# quad_sensor_adapter.net
KiCad netlist of a schematic drawn in EAGLE
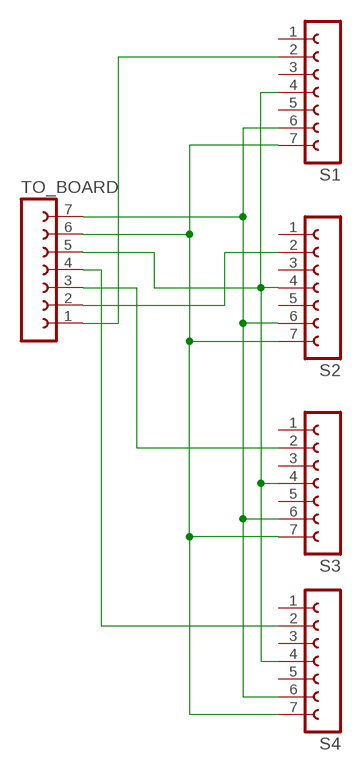
[diagram p0: schematic, sheet 1]

(export (version "E")
  (design (tool "Eeschema 10.0.6"))
  (components
    (comp (ref "S1")
      (value "FE07-1")
      (footprint "eagle-import:FE07")
      (libsource (lib "eagle-import") (part "FE07-1"))
    )
    (comp (ref "S2")
      (value "FE07-1")
      (footprint "eagle-import:FE07")
      (libsource (lib "eagle-import") (part "FE07-1"))
    )
    (comp (ref "S3")
      (value "FE07-1")
      (footprint "eagle-import:FE07")
      (libsource (lib "eagle-import") (part "FE07-1"))
    )
    (comp (ref "S4")
      (value "FE07-1")
      (footprint "eagle-import:FE07")
      (libsource (lib "eagle-import") (part "FE07-1"))
    )
    (comp (ref "TO_BOARD")
      (value "FE07-1")
      (footprint "eagle-import:FE07")
      (libsource (lib "eagle-import") (part "FE07-1"))
    )
  )
  (nets
    (net (code "1") (name "Net-(S1-Pad2)") (class "Default")
      (node (ref "S1") (pin "2") (pinfunction "2_2") (pintype "passive"))
      (node (ref "TO_BOARD") (pin "1") (pinfunction "1_1") (pintype "passive"))
    )
    (net (code "2") (name "Net-(S1-Pad4)") (class "Default")
      (node (ref "S1") (pin "4") (pinfunction "4_4") (pintype "passive"))
      (node (ref "S2") (pin "4") (pinfunction "4_4") (pintype "passive"))
      (node (ref "S3") (pin "4") (pinfunction "4_4") (pintype "passive"))
      (node (ref "S4") (pin "4") (pinfunction "4_4") (pintype "passive"))
      (node (ref "TO_BOARD") (pin "5") (pinfunction "5_5") (pintype "passive"))
    )
    (net (code "3") (name "Net-(S1-Pad6)") (class "Default")
      (node (ref "S1") (pin "6") (pinfunction "6_6") (pintype "passive"))
      (node (ref "S2") (pin "6") (pinfunction "6_6") (pintype "passive"))
      (node (ref "S3") (pin "6") (pinfunction "6_6") (pintype "passive"))
      (node (ref "S4") (pin "6") (pinfunction "6_6") (pintype "passive"))
      (node (ref "TO_BOARD") (pin "7") (pinfunction "7_7") (pintype "passive"))
    )
    (net (code "4") (name "Net-(S1-Pad7)") (class "Default")
      (node (ref "S1") (pin "7") (pinfunction "7_7") (pintype "passive"))
      (node (ref "S2") (pin "7") (pinfunction "7_7") (pintype "passive"))
      (node (ref "S3") (pin "7") (pinfunction "7_7") (pintype "passive"))
      (node (ref "S4") (pin "7") (pinfunction "7_7") (pintype "passive"))
      (node (ref "TO_BOARD") (pin "6") (pinfunction "6_6") (pintype "passive"))
    )
    (net (code "5") (name "Net-(S2-Pad2)") (class "Default")
      (node (ref "S2") (pin "2") (pinfunction "2_2") (pintype "passive"))
      (node (ref "TO_BOARD") (pin "2") (pinfunction "2_2") (pintype "passive"))
    )
    (net (code "6") (name "Net-(S3-Pad2)") (class "Default")
      (node (ref "S3") (pin "2") (pinfunction "2_2") (pintype "passive"))
      (node (ref "TO_BOARD") (pin "3") (pinfunction "3_3") (pintype "passive"))
    )
    (net (code "7") (name "Net-(S4-Pad2)") (class "Default")
      (node (ref "S4") (pin "2") (pinfunction "2_2") (pintype "passive"))
      (node (ref "TO_BOARD") (pin "4") (pinfunction "4_4") (pintype "passive"))
    )
    (net (code "8") (name "unconnected-(S1-Pad1)") (class "Default")
      (node (ref "S1") (pin "1") (pinfunction "1_1") (pintype "passive"))
    )
    (net (code "9") (name "unconnected-(S1-Pad3)") (class "Default")
      (node (ref "S1") (pin "3") (pinfunction "3_3") (pintype "passive"))
    )
    (net (code "10") (name "unconnected-(S1-Pad5)") (class "Default")
      (node (ref "S1") (pin "5") (pinfunction "5_5") (pintype "passive"))
    )
    (net (code "11") (name "unconnected-(S2-Pad1)") (class "Default")
      (node (ref "S2") (pin "1") (pinfunction "1_1") (pintype "passive"))
    )
    (net (code "12") (name "unconnected-(S2-Pad3)") (class "Default")
      (node (ref "S2") (pin "3") (pinfunction "3_3") (pintype "passive"))
    )
    (net (code "13") (name "unconnected-(S2-Pad5)") (class "Default")
      (node (ref "S2") (pin "5") (pinfunction "5_5") (pintype "passive"))
    )
    (net (code "14") (name "unconnected-(S3-Pad1)") (class "Default")
      (node (ref "S3") (pin "1") (pinfunction "1_1") (pintype "passive"))
    )
    (net (code "15") (name "unconnected-(S3-Pad3)") (class "Default")
      (node (ref "S3") (pin "3") (pinfunction "3_3") (pintype "passive"))
    )
    (net (code "16") (name "unconnected-(S3-Pad5)") (class "Default")
      (node (ref "S3") (pin "5") (pinfunction "5_5") (pintype "passive"))
    )
    (net (code "17") (name "unconnected-(S4-Pad1)") (class "Default")
      (node (ref "S4") (pin "1") (pinfunction "1_1") (pintype "passive"))
    )
    (net (code "18") (name "unconnected-(S4-Pad3)") (class "Default")
      (node (ref "S4") (pin "3") (pinfunction "3_3") (pintype "passive"))
    )
    (net (code "19") (name "unconnected-(S4-Pad5)") (class "Default")
      (node (ref "S4") (pin "5") (pinfunction "5_5") (pintype "passive"))
    )
  )
)
